# Schematic.net
KiCad netlist of a schematic drawn in Altium Designer
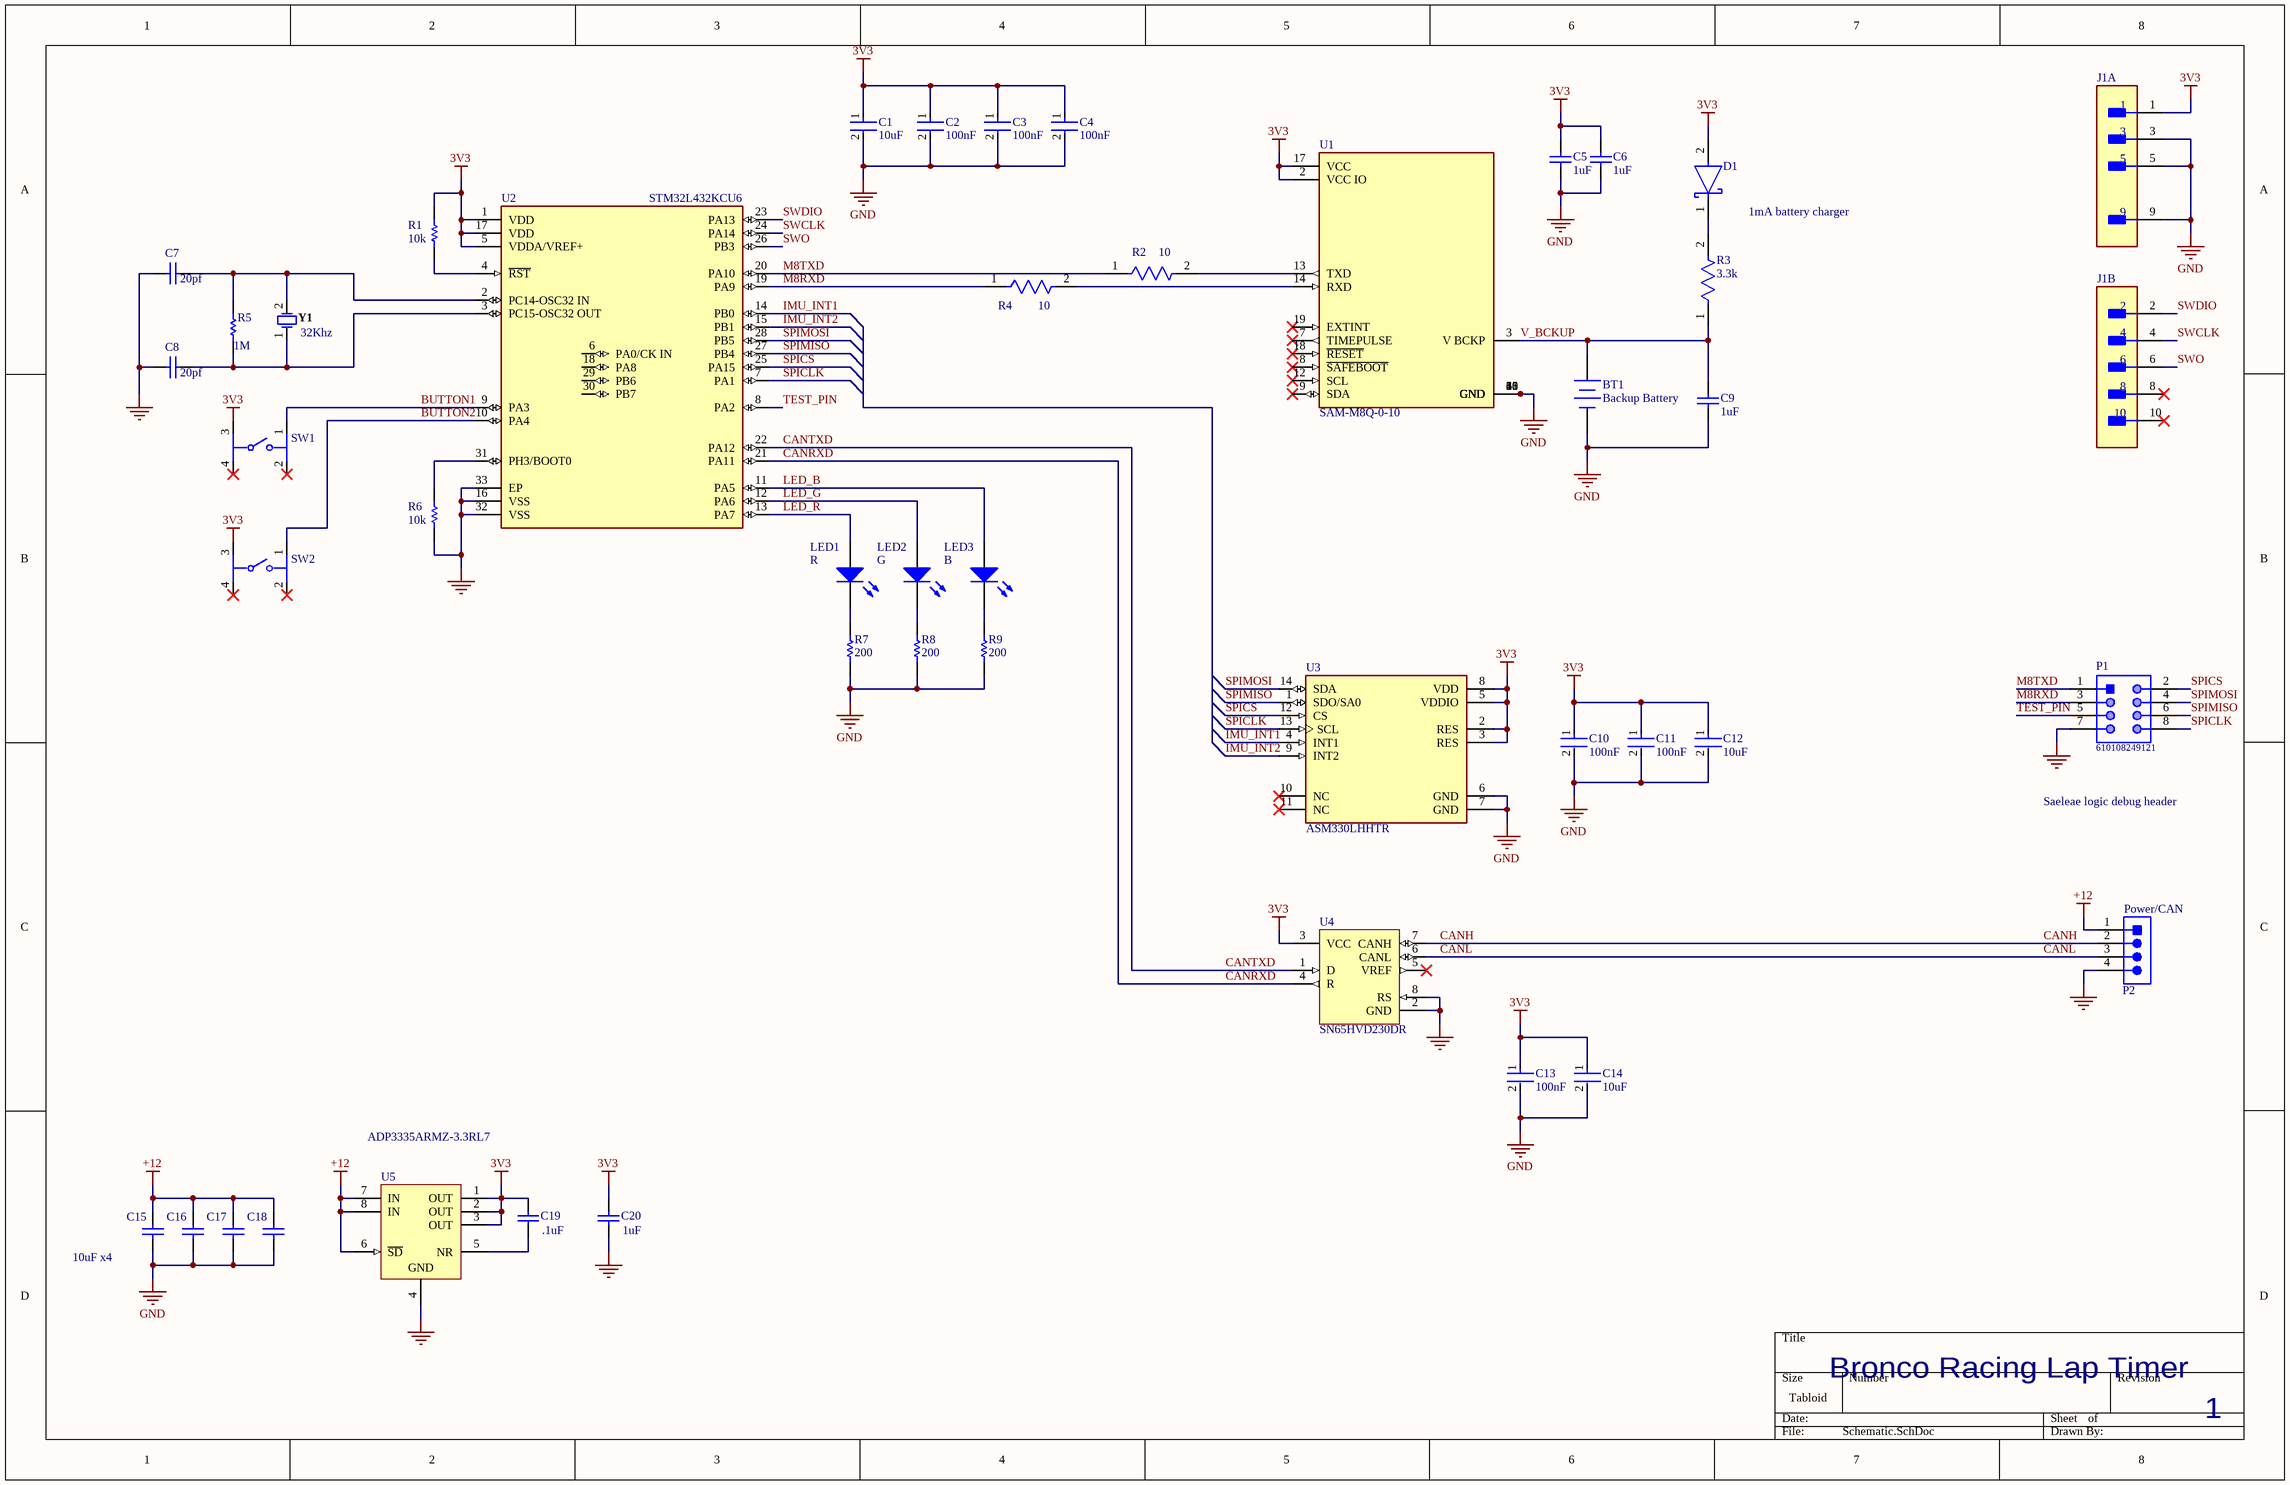
[diagram p0: Schematic.SchDoc]

(export (version "E")
  (design (tool "Eeschema 10.0.6"))
  (components
    (comp (ref "BT1")
      (value "Backup Battery")
      (footprint "SEIK-MS621FE-FL11E-2_V")
      (description "MS Lihium Rechargeable Battery, 3 V, -20 to 60 degC, Tray")
      (fields (field (name "MANUFACTURER") "SeikoInstruments"))
      (libsource (lib "Altium Content Vault") (part "BATTERY_SINGLE-2"))
    )
    (comp (ref "C1")
      (value "10uF")
      (footprint "FP-C1608-080-MFG")
      (description "CAP CER 10UF 10V X5R 0603")
      (fields
        (field (name "MANUFACTURER PART NUMBER") "C1608X5R1A106K080AC")
        (field (name "OCTOPART") "https://octopart.com/c1608x5r1a106k080ac-tdk-26013468")
      )
      (libsource (lib "Altium Content Vault") (part "11868f565c42a9108669ba33697ecf6"))
    )
    (comp (ref "C2")
      (value "100nF")
      (footprint "FP-CGA3E-0_3-0_1-IPC_A")
      (description "Cap Ceramic 100nF 50V X7R 10% Pad SMD 0603 +125°C Automotive T/R")
      (fields (field (name "TOLERANCE") "10%") (field (name "VOLTAGE") "50V"))
      (libsource (lib "Altium Content Vault") (part "b4654b650e69147ec39a6b967a45e02"))
    )
    (comp (ref "C3")
      (value "100nF")
      (footprint "FP-CGA3E-0_3-0_1-IPC_A")
      (description "Cap Ceramic 100nF 50V X7R 10% Pad SMD 0603 +125°C Automotive T/R")
      (fields (field (name "TOLERANCE") "10%") (field (name "VOLTAGE") "50V"))
      (libsource (lib "Altium Content Vault") (part "b4654b650e69147ec39a6b967a45e02"))
    )
    (comp (ref "C4")
      (value "100nF")
      (footprint "FP-CGA3E-0_3-0_1-IPC_A")
      (description "Cap Ceramic 100nF 50V X7R 10% Pad SMD 0603 +125°C Automotive T/R")
      (fields (field (name "TOLERANCE") "10%") (field (name "VOLTAGE") "50V"))
      (libsource (lib "Altium Content Vault") (part "b4654b650e69147ec39a6b967a45e02"))
    )
    (comp (ref "C5")
      (value "1uF")
      (footprint "CAPC1608X90X35LL15T15")
      (fields (field (name "MANUFACTURER") "Kemet") (field (name "PART NUMBER") "C0603C105K3PAC7867"))
      (libsource (lib "Altium Content Vault") (part "CAP"))
    )
    (comp (ref "C6")
      (value "1uF")
      (footprint "CAPC1608X90X35LL15T15")
      (fields (field (name "MANUFACTURER") "Kemet") (field (name "PART NUMBER") "C0603C105K3PAC7867"))
      (libsource (lib "Altium Content Vault") (part "CAP"))
    )
    (comp (ref "C7")
      (value "08051A200JAT2A")
      (footprint "CAPC2013X140X50NL20T25")
      (fields (field (name "MANUFACTURER") "AVX Interconnect / Elco"))
      (libsource (lib "Altium Content Vault") (part "CAP"))
    )
    (comp (ref "C8")
      (value "08051A200JAT2A")
      (footprint "CAPC2013X140X50NL20T25")
      (fields (field (name "MANUFACTURER") "AVX Interconnect / Elco"))
      (libsource (lib "Altium Content Vault") (part "CAP"))
    )
    (comp (ref "C9")
      (value "1uF")
      (footprint "CAPC1608X90X35LL15T15")
      (fields (field (name "MANUFACTURER") "Kemet") (field (name "PART NUMBER") "C0603C105K3PAC7867"))
      (libsource (lib "Altium Content Vault") (part "CAP"))
    )
    (comp (ref "C10")
      (value "100nF")
      (footprint "FP-CGA3E-0_3-0_1-IPC_A")
      (description "Cap Ceramic 100nF 50V X7R 10% Pad SMD 0603 +125°C Automotive T/R")
      (fields (field (name "TOLERANCE") "10%") (field (name "VOLTAGE") "50V"))
      (libsource (lib "Altium Content Vault") (part "b4654b650e69147ec39a6b967a45e02"))
    )
    (comp (ref "C11")
      (value "100nF")
      (footprint "FP-CGA3E-0_3-0_1-IPC_A")
      (description "Cap Ceramic 100nF 50V X7R 10% Pad SMD 0603 +125°C Automotive T/R")
      (fields (field (name "TOLERANCE") "10%") (field (name "VOLTAGE") "50V"))
      (libsource (lib "Altium Content Vault") (part "b4654b650e69147ec39a6b967a45e02"))
    )
    (comp (ref "C12")
      (value "10uF")
      (footprint "FP-C1608-080-MFG")
      (description "CAP CER 10UF 10V X5R 0603")
      (fields
        (field (name "MANUFACTURER PART NUMBER") "C1608X5R1A106K080AC")
        (field (name "OCTOPART") "https://octopart.com/c1608x5r1a106k080ac-tdk-26013468")
      )
      (libsource (lib "Altium Content Vault") (part "11868f565c42a9108669ba33697ecf6"))
    )
    (comp (ref "C13")
      (value "100nF")
      (footprint "FP-CGA3E-0_3-0_1-IPC_A")
      (description "Cap Ceramic 100nF 50V X7R 10% Pad SMD 0603 +125°C Automotive T/R")
      (fields (field (name "TOLERANCE") "10%") (field (name "VOLTAGE") "50V"))
      (libsource (lib "Altium Content Vault") (part "b4654b650e69147ec39a6b967a45e02"))
    )
    (comp (ref "C14")
      (value "10uF")
      (footprint "FP-C1608-080-MFG")
      (description "CAP CER 10UF 10V X5R 0603")
      (fields
        (field (name "MANUFACTURER PART NUMBER") "C1608X5R1A106K080AC")
        (field (name "OCTOPART") "https://octopart.com/c1608x5r1a106k080ac-tdk-26013468")
      )
      (libsource (lib "Altium Content Vault") (part "11868f565c42a9108669ba33697ecf6"))
    )
    (comp (ref "C15")
      (value "CGA5L3X5R1H106K160AB")
      (footprint "CAPC3216X190X20LL20")
      (description "Chip Capacitor, 10 uF, +/- 10%, 50 V, -55 to 85 degC, 1206 (3216 Metric), RoHS, Tape and Reel")
      (fields (field (name "MANUFACTURER") "TDK") (field (name "TOLERANCE") "10%"))
      (libsource (lib "Altium Content Vault") (part "CAP-NP-2"))
    )
    (comp (ref "C16")
      (value "CGA5L3X5R1H106K160AB")
      (footprint "CAPC3216X190X20LL20")
      (description "Chip Capacitor, 10 uF, +/- 10%, 50 V, -55 to 85 degC, 1206 (3216 Metric), RoHS, Tape and Reel")
      (fields (field (name "MANUFACTURER") "TDK") (field (name "TOLERANCE") "10%"))
      (libsource (lib "Altium Content Vault") (part "CAP-NP-2"))
    )
    (comp (ref "C17")
      (value "CGA5L3X5R1H106K160AB")
      (footprint "CAPC3216X190X20LL20")
      (description "Chip Capacitor, 10 uF, +/- 10%, 50 V, -55 to 85 degC, 1206 (3216 Metric), RoHS, Tape and Reel")
      (fields (field (name "MANUFACTURER") "TDK") (field (name "TOLERANCE") "10%"))
      (libsource (lib "Altium Content Vault") (part "CAP-NP-2"))
    )
    (comp (ref "C18")
      (value "CGA5L3X5R1H106K160AB")
      (footprint "CAPC3216X190X20LL20")
      (description "Chip Capacitor, 10 uF, +/- 10%, 50 V, -55 to 85 degC, 1206 (3216 Metric), RoHS, Tape and Reel")
      (fields (field (name "MANUFACTURER") "TDK") (field (name "TOLERANCE") "10%"))
      (libsource (lib "Altium Content Vault") (part "CAP-NP-2"))
    )
    (comp (ref "C19")
      (value "CGA3E2X7R1H104K080AA")
      (footprint "CAPC1608X90X20LL10")
      (description "Chip Capacitor, 0.1 uF, +/- 10%, 50 V, -55 to 125 degC, 0603 (1608 Metric), RoHS, Tape and Reel")
      (fields (field (name "VOLTAGE") "50V") (field (name "TOLERANCE") "10%"))
      (libsource (lib "Altium Content Vault") (part "CAP-NP-2"))
    )
    (comp (ref "C20")
      (value "GRM31MR71H105KA88L")
      (footprint "CAPC3216X125X55LL15T25")
      (description "Chip Capacitor, 1 uF, +/- 10%, 50 V, -55 to 125 degC, 1206 (3216 Metric), RoHS, Tape and Reel")
      (fields (field (name "TOLERANCE") "10%") (field (name "MANUFACTURER") "Murata"))
      (libsource (lib "Altium Content Vault") (part "CAP-NP-2"))
    )
    (comp (ref "D1")
      (value "SD0603S040S0R2")
      (footprint "FP-SD0603-MFG")
      (description "DIODE SCHOTTKY 40V 200MA 0603")
      (fields
        (field (name "MANUFACTURER") "AVX")
        (field (name "OCTOPART") "https://octopart.com/sd0603s040s0r2-avx-24931763")
      )
      (libsource (lib "Altium Content Vault") (part "1d6ec82d83fb6aee721767c19dac4b9"))
    )
    (comp (ref "J1")
      (value "FTSH-105-01-L-DV-007-K")
      (footprint "FP-FTSH-105-01-L-DV-007-K-MFG")
      (description "CONN HEADER SMD 10POS 1.27MM")
      (fields
        (field (name "OCTOPART") "https://octopart.com/ftsh-105-01-l-dv-007-k-samtec-53647300")
        (field (name "MANUFACTURER") "Samtec")
      )
      (libsource (lib "Altium Content Vault") (part "7c368be3265735b2816d0cab4417f87"))
    )
    (comp (ref "LED1")
      (value "150120RS75000")
      (footprint "1206_A")
      (description "SMD mono-color Chip LED, WL-SMCW, Red")
      (fields (field (name "MANUFACTURER") "Wuerth Elektronik"))
      (libsource (lib "Altium Content Vault") (part "WE-LED_K1A2-2"))
    )
    (comp (ref "LED2")
      (value "150120GS75000")
      (footprint "1206_A")
      (description "SMD mono-color Chip LED, WL-SMCW, Green")
      (fields (field (name "MANUFACTURER") "Wuerth Elektronik"))
      (libsource (lib "Altium Content Vault") (part "WE-LED_K1A2-2"))
    )
    (comp (ref "LED3")
      (value "150120BS75000")
      (footprint "1206_A")
      (description "SMD mono-color Chip LED, WL-SMCW, Blue")
      (fields (field (name "MANUFACTURER") "Wuerth Elektronik"))
      (libsource (lib "Altium Content Vault") (part "WE-LED_K1A2-2"))
    )
    (comp (ref "P1")
      (value "610108249121")
      (footprint "610108249121")
      (description "SMT Angled Pin Header WR-PHD, Pitch 2.54 mm, Dual Row, 8 pins")
      (fields (field (name "MANUFACTURER") "Wurth Elektronik") (field (name "PUBLISHER") "WurthElektronik"))
      (libsource (lib "Altium Content Vault") (part "WE-CN-2P-M-R8"))
    )
    (comp (ref "P2")
      (value "B4B-PH-K-S(LF)(SN)")
      (footprint "JST-B4B-PH-K-S_V")
      (fields (field (name "MANUFACTURER") "JST"))
      (libsource (lib "Altium Content Vault") (part "CN-1P-M-R4"))
    )
    (comp (ref "R1")
      (value "10k")
      (footprint "RESC1609X55X30LL15T15")
      (description "Chip Resistor, 10 KOhm, +/- 1%, 0.1 W, -55 to 155 degC, 0603 (1608 Metric), RoHS, Tape and Reel")
      (fields (field (name "TOLERANCE") "1%") (field (name "MANUFACTURER") "Panasonic"))
      (libsource (lib "Altium Content Vault") (part "RES-2"))
    )
    (comp (ref "R2")
      (value "10")
      (footprint "FP-RT0603-MFG")
      (description "RES SMD 10 OHM 0.1% 1/10W 0603")
      (fields (field (name "TOLERANCE") "0.001") (field (name "MANUFACTURER") "Yageo"))
      (libsource (lib "Altium Content Vault") (part "1029c3af85768c4190bb7ad29bc67b5"))
    )
    (comp (ref "R3")
      (value "3.3k")
      (footprint "FP-RT0603-MFG")
      (description "RES 3.30K OHM 1/10W 1% SMD 0603")
      (fields
        (field (name "OCTOPART") "https://octopart.com/rt0603fre073k3l-yageo-39814754")
        (field (name "MANUFACTURER PART NUMBER") "RT0603FRE073K3L")
      )
      (libsource (lib "Altium Content Vault") (part "1029c3af85768c4190bb7ad29bc67b5"))
    )
    (comp (ref "R4")
      (value "10")
      (footprint "FP-RT0603-MFG")
      (description "RES SMD 10 OHM 0.1% 1/10W 0603")
      (fields (field (name "TOLERANCE") "0.001") (field (name "MANUFACTURER") "Yageo"))
      (libsource (lib "Altium Content Vault") (part "1029c3af85768c4190bb7ad29bc67b5"))
    )
    (comp (ref "R5")
      (value "ERJ-8ENF1004V")
      (footprint "RESC3216X70X50NL05T20")
      (fields (field (name "MANUFACTURER") "Panasonic"))
      (libsource (lib "Altium Content Vault") (part "RES"))
    )
    (comp (ref "R6")
      (value "10k")
      (footprint "RESC1609X55X30LL15T15")
      (description "Chip Resistor, 10 KOhm, +/- 1%, 0.1 W, -55 to 155 degC, 0603 (1608 Metric), RoHS, Tape and Reel")
      (fields (field (name "TOLERANCE") "1%") (field (name "MANUFACTURER") "Panasonic"))
      (libsource (lib "Altium Content Vault") (part "RES-2"))
    )
    (comp (ref "R7")
      (value "200")
      (footprint "RESC1609X55X30NL10T20")
      (fields (field (name "PART NUMBER") "TNPW0603200RBEEA") (field (name "MANUFACTURER") "Vishay Dale"))
      (libsource (lib "Altium Content Vault") (part "RES"))
    )
    (comp (ref "R8")
      (value "200")
      (footprint "RESC1609X55X30NL10T20")
      (fields (field (name "PART NUMBER") "TNPW0603200RBEEA") (field (name "MANUFACTURER") "Vishay Dale"))
      (libsource (lib "Altium Content Vault") (part "RES"))
    )
    (comp (ref "R9")
      (value "200")
      (footprint "RESC1609X55X30NL10T20")
      (fields (field (name "PART NUMBER") "TNPW0603200RBEEA") (field (name "MANUFACTURER") "Vishay Dale"))
      (libsource (lib "Altium Content Vault") (part "RES"))
    )
    (comp (ref "SW1")
      (value "PTS645SM43SMTR92LFS")
      (footprint "FP-PTS645SM43SMTR92LFS-MFG")
      (description "SWITCH TACTILE SPST-NO 0.05A 12V")
      (libsource (lib "Altium Content Vault") (part "1adf0dd01260c80cf25a44bfd6b99ba"))
    )
    (comp (ref "SW2")
      (value "PTS645SM43SMTR92LFS")
      (footprint "FP-PTS645SM43SMTR92LFS-MFG")
      (description "SWITCH TACTILE SPST-NO 0.05A 12V")
      (libsource (lib "Altium Content Vault") (part "1adf0dd01260c80cf25a44bfd6b99ba"))
    )
    (comp (ref "U1")
      (value "SAM-M8Q-0-10")
      (footprint "FP-SAM-M8Q-0-10-MFG")
      (description "RF RX GALILEO 1.575GHZ/1.602GHZ")
      (fields
        (field (name "MANUFACTURER") "uBlox")
        (field (name "OCTOPART") "https://octopart.com/sam-m8q-0-10-u-blox-88247750")
      )
      (libsource (lib "Altium Content Vault") (part "e897669bc61729ed63f6e62e0b1e840"))
    )
    (comp (ref "U2")
      (value "STM32L432KCU6")
      (footprint "FP-UFQFPN32-A0B8-MFG")
      (description "IC MCU 32BIT 256KB FLASH 32QFPN")
      (fields
        (field (name "OCTOPART") "https://octopart.com/stm32l432kcu6-stmicroelectronics-71093510")
        (field (name "MANUFACTURER") "STMicroelectronics")
      )
      (libsource (lib "Altium Content Vault") (part "f3240dca552e0aa49c1b4baba198c12"))
    )
    (comp (ref "U3")
      (value "ASM330LHHTR")
      (footprint "FP-LGA-14L-DM00249496-MFG")
      (description "AUTOMOTIVE 6-AXIS INERTIAL MODUL")
      (fields
        (field (name "MANUFACTURER") "STMicroelectronics")
        (field (name "OCTOPART") "https://octopart.com/asm330lhhtr-stmicroelectronics-93180171")
      )
      (libsource (lib "Altium Content Vault") (part "0de4c904e7ecf2841643ad1a6a46911"))
    )
    (comp (ref "U4")
      (value "SN65HVD230DR")
      (footprint "D0008A_L")
      (fields (field (name "MANUFACTURER") "Texas Instruments"))
      (libsource (lib "Altium Content Vault") (part "TI-SN65HVD230-SOIC_D-8"))
    )
    (comp (ref "U5")
      (value "ADP3335ARMZ-3.3RL7")
      (footprint "ADI-RM-8_L")
      (fields (field (name "MANUFACTURER") "Analog Devices"))
      (libsource (lib "Altium Content Vault") (part "ADI-ADP3335-RM-8"))
    )
    (comp (ref "Y1")
      (value "ABS07-120-32.768KHZ-T")
      (footprint "ABRA-ABS07_A_V")
      (description "Tuning Fork Crystal, 32.768 KHz, +/- 20 ppm, -40 to 85 degC, 2-Pin SMD, RoHS, Tape and Reel")
      (fields (field (name "MANUFACTURER") "Abracon") (field (name "TOLERANCE") "20ppm"))
      (libsource (lib "Altium Content Vault") (part "XTAL-1-2-2"))
    )
  )
  (nets
    (net (code "1") (name "+12") (class "Default")
      (node (ref "C15") (pin "1") (pinfunction "1_1") (pintype "passive"))
      (node (ref "C16") (pin "1") (pinfunction "1_1") (pintype "passive"))
      (node (ref "C17") (pin "1") (pinfunction "1_1") (pintype "passive"))
      (node (ref "C18") (pin "1") (pinfunction "1_1") (pintype "passive"))
      (node (ref "P2") (pin "1") (pinfunction "1_1") (pintype "passive"))
      (node (ref "U5") (pin "6") (pinfunction "~{SD}_6") (pintype "input"))
      (node (ref "U5") (pin "7") (pinfunction "IN_7") (pintype "power_in"))
      (node (ref "U5") (pin "8") (pinfunction "IN_8") (pintype "power_in"))
    )
    (net (code "3") (name "/BUTTON1") (class "Default")
      (node (ref "SW1") (pin "1") (pinfunction "1_1") (pintype "passive"))
      (node (ref "U2") (pin "9") (pinfunction "PA3_9") (pintype "bidirectional"))
    )
    (net (code "4") (name "/BUTTON2") (class "Default")
      (node (ref "SW2") (pin "1") (pinfunction "1_1") (pintype "passive"))
      (node (ref "U2") (pin "10") (pinfunction "PA4_10") (pintype "bidirectional"))
    )
    (net (code "5") (name "/CANH") (class "Default")
      (node (ref "P2") (pin "2") (pinfunction "2_2") (pintype "passive"))
      (node (ref "U4") (pin "7") (pinfunction "CANH_7") (pintype "bidirectional"))
    )
    (net (code "6") (name "/CANL") (class "Default")
      (node (ref "P2") (pin "3") (pinfunction "3_3") (pintype "passive"))
      (node (ref "U4") (pin "6") (pinfunction "CANL_6") (pintype "bidirectional"))
    )
    (net (code "7") (name "/CANRXD") (class "Default")
      (node (ref "U2") (pin "21") (pinfunction "PA11_21") (pintype "bidirectional"))
      (node (ref "U4") (pin "4") (pinfunction "R_4") (pintype "output"))
    )
    (net (code "8") (name "/CANTXD") (class "Default")
      (node (ref "U2") (pin "22") (pinfunction "PA12_22") (pintype "bidirectional"))
      (node (ref "U4") (pin "1") (pinfunction "D_1") (pintype "input"))
    )
    (net (code "9") (name "/IMU_INT1") (class "Default")
      (node (ref "U2") (pin "14") (pinfunction "PB0_14") (pintype "bidirectional"))
      (node (ref "U3") (pin "4") (pinfunction "INT1_4") (pintype "input"))
    )
    (net (code "10") (name "/IMU_INT2") (class "Default")
      (node (ref "U2") (pin "15") (pinfunction "PB1_15") (pintype "bidirectional"))
      (node (ref "U3") (pin "9") (pinfunction "INT2_9") (pintype "input"))
    )
    (net (code "11") (name "/LED_B") (class "Default")
      (node (ref "LED3") (pin "2") (pinfunction "A_2") (pintype "passive"))
      (node (ref "U2") (pin "11") (pinfunction "PA5_11") (pintype "bidirectional"))
    )
    (net (code "12") (name "/LED_G") (class "Default")
      (node (ref "LED2") (pin "2") (pinfunction "A_2") (pintype "passive"))
      (node (ref "U2") (pin "12") (pinfunction "PA6_12") (pintype "bidirectional"))
    )
    (net (code "13") (name "/LED_R") (class "Default")
      (node (ref "LED1") (pin "2") (pinfunction "A_2") (pintype "passive"))
      (node (ref "U2") (pin "13") (pinfunction "PA7_13") (pintype "bidirectional"))
    )
    (net (code "14") (name "/M8RXD") (class "Default")
      (node (ref "P1") (pin "3") (pinfunction "3_3") (pintype "passive"))
      (node (ref "R4") (pin "1") (pinfunction "1_1") (pintype "passive"))
      (node (ref "U2") (pin "19") (pinfunction "PA9_19") (pintype "bidirectional"))
    )
    (net (code "15") (name "/M8TXD") (class "Default")
      (node (ref "P1") (pin "1") (pinfunction "1_1") (pintype "passive"))
      (node (ref "R2") (pin "1") (pinfunction "1_1") (pintype "passive"))
      (node (ref "U2") (pin "20") (pinfunction "PA10_20") (pintype "bidirectional"))
    )
    (net (code "16") (name "/SPICLK") (class "Default")
      (node (ref "P1") (pin "8") (pinfunction "8_8") (pintype "passive"))
      (node (ref "U2") (pin "7") (pinfunction "PA1_7") (pintype "bidirectional"))
      (node (ref "U3") (pin "13") (pinfunction "SCL_13") (pintype "input"))
    )
    (net (code "17") (name "/SPICS") (class "Default")
      (node (ref "P1") (pin "2") (pinfunction "2_2") (pintype "passive"))
      (node (ref "U2") (pin "25") (pinfunction "PA15_25") (pintype "bidirectional"))
      (node (ref "U3") (pin "12") (pinfunction "CS_12") (pintype "input"))
    )
    (net (code "18") (name "/SPIMISO") (class "Default")
      (node (ref "P1") (pin "6") (pinfunction "6_6") (pintype "passive"))
      (node (ref "U2") (pin "27") (pinfunction "PB4_27") (pintype "bidirectional"))
      (node (ref "U3") (pin "1") (pinfunction "SDO/SA0_1") (pintype "bidirectional"))
    )
    (net (code "19") (name "/SPIMOSI") (class "Default")
      (node (ref "P1") (pin "4") (pinfunction "4_4") (pintype "passive"))
      (node (ref "U2") (pin "28") (pinfunction "PB5_28") (pintype "bidirectional"))
      (node (ref "U3") (pin "14") (pinfunction "SDA_14") (pintype "bidirectional"))
    )
    (net (code "20") (name "/SWCLK") (class "Default")
      (node (ref "J1") (pin "4") (pinfunction "4_4") (pintype "passive"))
      (node (ref "U2") (pin "24") (pinfunction "PA14_24") (pintype "bidirectional"))
    )
    (net (code "21") (name "/SWDIO") (class "Default")
      (node (ref "J1") (pin "2") (pinfunction "2_2") (pintype "passive"))
      (node (ref "U2") (pin "23") (pinfunction "PA13_23") (pintype "bidirectional"))
    )
    (net (code "22") (name "/SWO") (class "Default")
      (node (ref "J1") (pin "6") (pinfunction "6_6") (pintype "passive"))
      (node (ref "U2") (pin "26") (pinfunction "PB3_26") (pintype "bidirectional"))
    )
    (net (code "23") (name "/TEST_PIN") (class "Default")
      (node (ref "P1") (pin "5") (pinfunction "5_5") (pintype "passive"))
      (node (ref "U2") (pin "8") (pinfunction "PA2_8") (pintype "bidirectional"))
    )
    (net (code "24") (name "/V_BCKUP") (class "Default")
      (node (ref "BT1") (pin "1") (pinfunction "+_1") (pintype "passive"))
      (node (ref "C9") (pin "2") (pinfunction "2_2") (pintype "passive"))
      (node (ref "R3") (pin "1") (pinfunction "1_1") (pintype "passive"))
      (node (ref "U1") (pin "3") (pinfunction "V_BCKP_3") (pintype "power_in"))
    )
    (net (code "25") (name "3V3") (class "Default")
      (node (ref "C1") (pin "1") (pinfunction "1_1") (pintype "passive"))
      (node (ref "C10") (pin "1") (pinfunction "1_1") (pintype "passive"))
      (node (ref "C11") (pin "1") (pinfunction "1_1") (pintype "passive"))
      (node (ref "C12") (pin "1") (pinfunction "1_1") (pintype "passive"))
      (node (ref "C13") (pin "1") (pinfunction "1_1") (pintype "passive"))
      (node (ref "C14") (pin "1") (pinfunction "1_1") (pintype "passive"))
      (node (ref "C19") (pin "1") (pinfunction "1_1") (pintype "passive"))
      (node (ref "C2") (pin "1") (pinfunction "1_1") (pintype "passive"))
      (node (ref "C20") (pin "1") (pinfunction "1_1") (pintype "passive"))
      (node (ref "C3") (pin "1") (pinfunction "1_1") (pintype "passive"))
      (node (ref "C4") (pin "1") (pinfunction "1_1") (pintype "passive"))
      (node (ref "C5") (pin "2") (pinfunction "2_2") (pintype "passive"))
      (node (ref "C6") (pin "2") (pinfunction "2_2") (pintype "passive"))
      (node (ref "D1") (pin "2") (pinfunction "A_2") (pintype "passive"))
      (node (ref "J1") (pin "1") (pinfunction "1_1") (pintype "passive"))
      (node (ref "R1") (pin "1") (pinfunction "1_1") (pintype "passive"))
      (node (ref "SW1") (pin "3") (pinfunction "3_3") (pintype "passive"))
      (node (ref "SW2") (pin "3") (pinfunction "3_3") (pintype "passive"))
      (node (ref "U1") (pin "17") (pinfunction "VCC_17") (pintype "power_in"))
      (node (ref "U1") (pin "2") (pinfunction "VCC_IO_2") (pintype "power_in"))
      (node (ref "U2") (pin "1") (pinfunction "VDD_1") (pintype "power_in"))
      (node (ref "U2") (pin "17") (pinfunction "VDD_17") (pintype "power_in"))
      (node (ref "U2") (pin "5") (pinfunction "VDDA/VREF+_5") (pintype "power_in"))
      (node (ref "U3") (pin "2") (pinfunction "RES_2") (pintype "passive"))
      (node (ref "U3") (pin "3") (pinfunction "RES_3") (pintype "passive"))
      (node (ref "U3") (pin "5") (pinfunction "VDDIO_5") (pintype "power_in"))
      (node (ref "U3") (pin "8") (pinfunction "VDD_8") (pintype "power_in"))
      (node (ref "U4") (pin "3") (pinfunction "VCC_3") (pintype "power_in"))
      (node (ref "U5") (pin "1") (pinfunction "OUT_1") (pintype "power_in"))
      (node (ref "U5") (pin "2") (pinfunction "OUT_2") (pintype "power_in"))
      (node (ref "U5") (pin "3") (pinfunction "OUT_3") (pintype "power_in"))
    )
    (net (code "26") (name "GND") (class "Default")
      (node (ref "BT1") (pin "2") (pinfunction "-_2") (pintype "passive"))
      (node (ref "C1") (pin "2") (pinfunction "2_2") (pintype "passive"))
      (node (ref "C10") (pin "2") (pinfunction "2_2") (pintype "passive"))
      (node (ref "C11") (pin "2") (pinfunction "2_2") (pintype "passive"))
      (node (ref "C12") (pin "2") (pinfunction "2_2") (pintype "passive"))
      (node (ref "C13") (pin "2") (pinfunction "2_2") (pintype "passive"))
      (node (ref "C14") (pin "2") (pinfunction "2_2") (pintype "passive"))
      (node (ref "C15") (pin "2") (pinfunction "2_2") (pintype "passive"))
      (node (ref "C16") (pin "2") (pinfunction "2_2") (pintype "passive"))
      (node (ref "C17") (pin "2") (pinfunction "2_2") (pintype "passive"))
      (node (ref "C18") (pin "2") (pinfunction "2_2") (pintype "passive"))
      (node (ref "C2") (pin "2") (pinfunction "2_2") (pintype "passive"))
      (node (ref "C20") (pin "2") (pinfunction "2_2") (pintype "passive"))
      (node (ref "C3") (pin "2") (pinfunction "2_2") (pintype "passive"))
      (node (ref "C4") (pin "2") (pinfunction "2_2") (pintype "passive"))
      (node (ref "C5") (pin "1") (pinfunction "1_1") (pintype "passive"))
      (node (ref "C6") (pin "1") (pinfunction "1_1") (pintype "passive"))
      (node (ref "C7") (pin "1") (pinfunction "1_1") (pintype "passive"))
      (node (ref "C8") (pin "1") (pinfunction "1_1") (pintype "passive"))
      (node (ref "C9") (pin "1") (pinfunction "1_1") (pintype "passive"))
      (node (ref "J1") (pin "3") (pinfunction "3_3") (pintype "passive"))
      (node (ref "J1") (pin "5") (pinfunction "5_5") (pintype "passive"))
      (node (ref "J1") (pin "9") (pinfunction "9_9") (pintype "passive"))
      (node (ref "P1") (pin "7") (pinfunction "7_7") (pintype "passive"))
      (node (ref "P2") (pin "4") (pinfunction "4_4") (pintype "passive"))
      (node (ref "R6") (pin "2") (pinfunction "2_2") (pintype "passive"))
      (node (ref "R7") (pin "1") (pinfunction "1_1") (pintype "passive"))
      (node (ref "R8") (pin "1") (pinfunction "1_1") (pintype "passive"))
      (node (ref "R9") (pin "1") (pinfunction "1_1") (pintype "passive"))
      (node (ref "U1") (pin "1") (pinfunction "GND_1") (pintype "power_in"))
      (node (ref "U1") (pin "10") (pinfunction "GND_10") (pintype "power_in"))
      (node (ref "U1") (pin "11") (pinfunction "GND_11") (pintype "power_in"))
      (node (ref "U1") (pin "15") (pinfunction "GND_15") (pintype "power_in"))
      (node (ref "U1") (pin "16") (pinfunction "GND_16") (pintype "power_in"))
      (node (ref "U1") (pin "20") (pinfunction "GND_20") (pintype "power_in"))
      (node (ref "U1") (pin "4") (pinfunction "GND_4") (pintype "power_in"))
      (node (ref "U1") (pin "5") (pinfunction "GND_5") (pintype "power_in"))
      (node (ref "U1") (pin "6") (pinfunction "GND_6") (pintype "power_in"))
      (node (ref "U2") (pin "16") (pinfunction "VSS_16") (pintype "power_in"))
      (node (ref "U2") (pin "32") (pinfunction "VSS_32") (pintype "power_in"))
      (node (ref "U2") (pin "33") (pinfunction "EP_33") (pintype "power_in"))
      (node (ref "U3") (pin "6") (pinfunction "GND_6") (pintype "power_in"))
      (node (ref "U3") (pin "7") (pinfunction "GND_7") (pintype "power_in"))
      (node (ref "U4") (pin "2") (pinfunction "GND_2") (pintype "power_in"))
      (node (ref "U4") (pin "8") (pinfunction "RS_8") (pintype "input"))
      (node (ref "U5") (pin "4") (pinfunction "GND_4") (pintype "power_in"))
    )
    (net (code "27") (name "Net-(D1-C)") (class "Default")
      (node (ref "D1") (pin "1") (pinfunction "C_1") (pintype "passive"))
      (node (ref "R3") (pin "2") (pinfunction "2_2") (pintype "passive"))
    )
    (net (code "28") (name "Net-(LED1-K)") (class "Default")
      (node (ref "LED1") (pin "1") (pinfunction "K_1") (pintype "passive"))
      (node (ref "R7") (pin "2") (pinfunction "2_2") (pintype "passive"))
    )
    (net (code "29") (name "Net-(LED2-K)") (class "Default")
      (node (ref "LED2") (pin "1") (pinfunction "K_1") (pintype "passive"))
      (node (ref "R8") (pin "2") (pinfunction "2_2") (pintype "passive"))
    )
    (net (code "30") (name "Net-(LED3-K)") (class "Default")
      (node (ref "LED3") (pin "1") (pinfunction "K_1") (pintype "passive"))
      (node (ref "R9") (pin "2") (pinfunction "2_2") (pintype "passive"))
    )
    (net (code "31") (name "Net-(U1-RXD)") (class "Default")
      (node (ref "R4") (pin "2") (pinfunction "2_2") (pintype "passive"))
      (node (ref "U1") (pin "14") (pinfunction "RXD_14") (pintype "input"))
    )
    (net (code "32") (name "Net-(U1-TXD)") (class "Default")
      (node (ref "R2") (pin "2") (pinfunction "2_2") (pintype "passive"))
      (node (ref "U1") (pin "13") (pinfunction "TXD_13") (pintype "output"))
    )
    (net (code "33") (name "Net-(U2-PC14-OSC32_IN)") (class "Default")
      (node (ref "C7") (pin "2") (pinfunction "2_2") (pintype "passive"))
      (node (ref "R5") (pin "1") (pinfunction "1_1") (pintype "passive"))
      (node (ref "U2") (pin "2") (pinfunction "PC14-OSC32_IN_2") (pintype "bidirectional"))
      (node (ref "Y1") (pin "2") (pinfunction "2_2") (pintype "passive"))
    )
    (net (code "34") (name "Net-(U2-PC15-OSC32_OUT)") (class "Default")
      (node (ref "C8") (pin "2") (pinfunction "2_2") (pintype "passive"))
      (node (ref "R5") (pin "2") (pinfunction "2_2") (pintype "passive"))
      (node (ref "U2") (pin "3") (pinfunction "PC15-OSC32_OUT_3") (pintype "bidirectional"))
      (node (ref "Y1") (pin "1") (pinfunction "1_1") (pintype "passive"))
    )
    (net (code "35") (name "Net-(U2-PH3{slash}BOOT0)") (class "Default")
      (node (ref "R6") (pin "1") (pinfunction "1_1") (pintype "passive"))
      (node (ref "U2") (pin "31") (pinfunction "PH3/BOOT0_31") (pintype "bidirectional"))
    )
    (net (code "36") (name "Net-(U2-~{RST})") (class "Default")
      (node (ref "R1") (pin "2") (pinfunction "2_2") (pintype "passive"))
      (node (ref "U2") (pin "4") (pinfunction "~{RST}_4") (pintype "input"))
    )
    (net (code "37") (name "Net-(U5-NR)") (class "Default")
      (node (ref "C19") (pin "2") (pinfunction "2_2") (pintype "passive"))
      (node (ref "U5") (pin "5") (pinfunction "NR_5") (pintype "passive"))
    )
    (net (code "38") (name "unconnected-(J1-Pad8)") (class "Default")
      (node (ref "J1") (pin "8") (pinfunction "8_8") (pintype "passive+no_connect"))
    )
    (net (code "39") (name "unconnected-(J1-Pad10)") (class "Default")
      (node (ref "J1") (pin "10") (pinfunction "10_10") (pintype "passive+no_connect"))
    )
    (net (code "40") (name "unconnected-(SW1-Pad2)") (class "Default")
      (node (ref "SW1") (pin "2") (pinfunction "2_2") (pintype "passive+no_connect"))
    )
    (net (code "41") (name "unconnected-(SW1-Pad4)") (class "Default")
      (node (ref "SW1") (pin "4") (pinfunction "4_4") (pintype "passive+no_connect"))
    )
    (net (code "42") (name "unconnected-(SW2-Pad2)") (class "Default")
      (node (ref "SW2") (pin "2") (pinfunction "2_2") (pintype "passive+no_connect"))
    )
    (net (code "43") (name "unconnected-(SW2-Pad4)") (class "Default")
      (node (ref "SW2") (pin "4") (pinfunction "4_4") (pintype "passive+no_connect"))
    )
    (net (code "44") (name "unconnected-(U1-EXTINT-Pad19)") (class "Default")
      (node (ref "U1") (pin "19") (pinfunction "EXTINT_19") (pintype "input+no_connect"))
    )
    (net (code "45") (name "unconnected-(U1-SCL-Pad12)") (class "Default")
      (node (ref "U1") (pin "12") (pinfunction "SCL_12") (pintype "input+no_connect"))
    )
    (net (code "46") (name "unconnected-(U1-SDA-Pad9)") (class "Default")
      (node (ref "U1") (pin "9") (pinfunction "SDA_9") (pintype "bidirectional+no_connect"))
    )
    (net (code "47") (name "unconnected-(U1-TIMEPULSE-Pad7)") (class "Default")
      (node (ref "U1") (pin "7") (pinfunction "TIMEPULSE_7") (pintype "output+no_connect"))
    )
    (net (code "48") (name "unconnected-(U1-~{RESET}-Pad18)") (class "Default")
      (node (ref "U1") (pin "18") (pinfunction "~{RESET}_18") (pintype "input+no_connect"))
    )
    (net (code "49") (name "unconnected-(U1-~{SAFEBOOT}-Pad8)") (class "Default")
      (node (ref "U1") (pin "8") (pinfunction "~{SAFEBOOT}_8") (pintype "input+no_connect"))
    )
    (net (code "50") (name "unconnected-(U2-PA0{slash}CK_IN-Pad6)") (class "Default")
      (node (ref "U2") (pin "6") (pinfunction "PA0/CK_IN_6") (pintype "bidirectional"))
    )
    (net (code "51") (name "unconnected-(U2-PA8-Pad18)") (class "Default")
      (node (ref "U2") (pin "18") (pinfunction "PA8_18") (pintype "bidirectional"))
    )
    (net (code "52") (name "unconnected-(U2-PB6-Pad29)") (class "Default")
      (node (ref "U2") (pin "29") (pinfunction "PB6_29") (pintype "bidirectional"))
    )
    (net (code "53") (name "unconnected-(U2-PB7-Pad30)") (class "Default")
      (node (ref "U2") (pin "30") (pinfunction "PB7_30") (pintype "bidirectional"))
    )
    (net (code "54") (name "unconnected-(U3-NC-Pad10)") (class "Default")
      (node (ref "U3") (pin "10") (pinfunction "NC_10") (pintype "passive+no_connect"))
    )
    (net (code "55") (name "unconnected-(U3-NC-Pad11)") (class "Default")
      (node (ref "U3") (pin "11") (pinfunction "NC_11") (pintype "passive+no_connect"))
    )
    (net (code "56") (name "unconnected-(U4-VREF-Pad5)") (class "Default")
      (node (ref "U4") (pin "5") (pinfunction "VREF_5") (pintype "output+no_connect"))
    )
  )
)
